# Comparator.net
KiCad netlist of a schematic drawn in Altium Designer
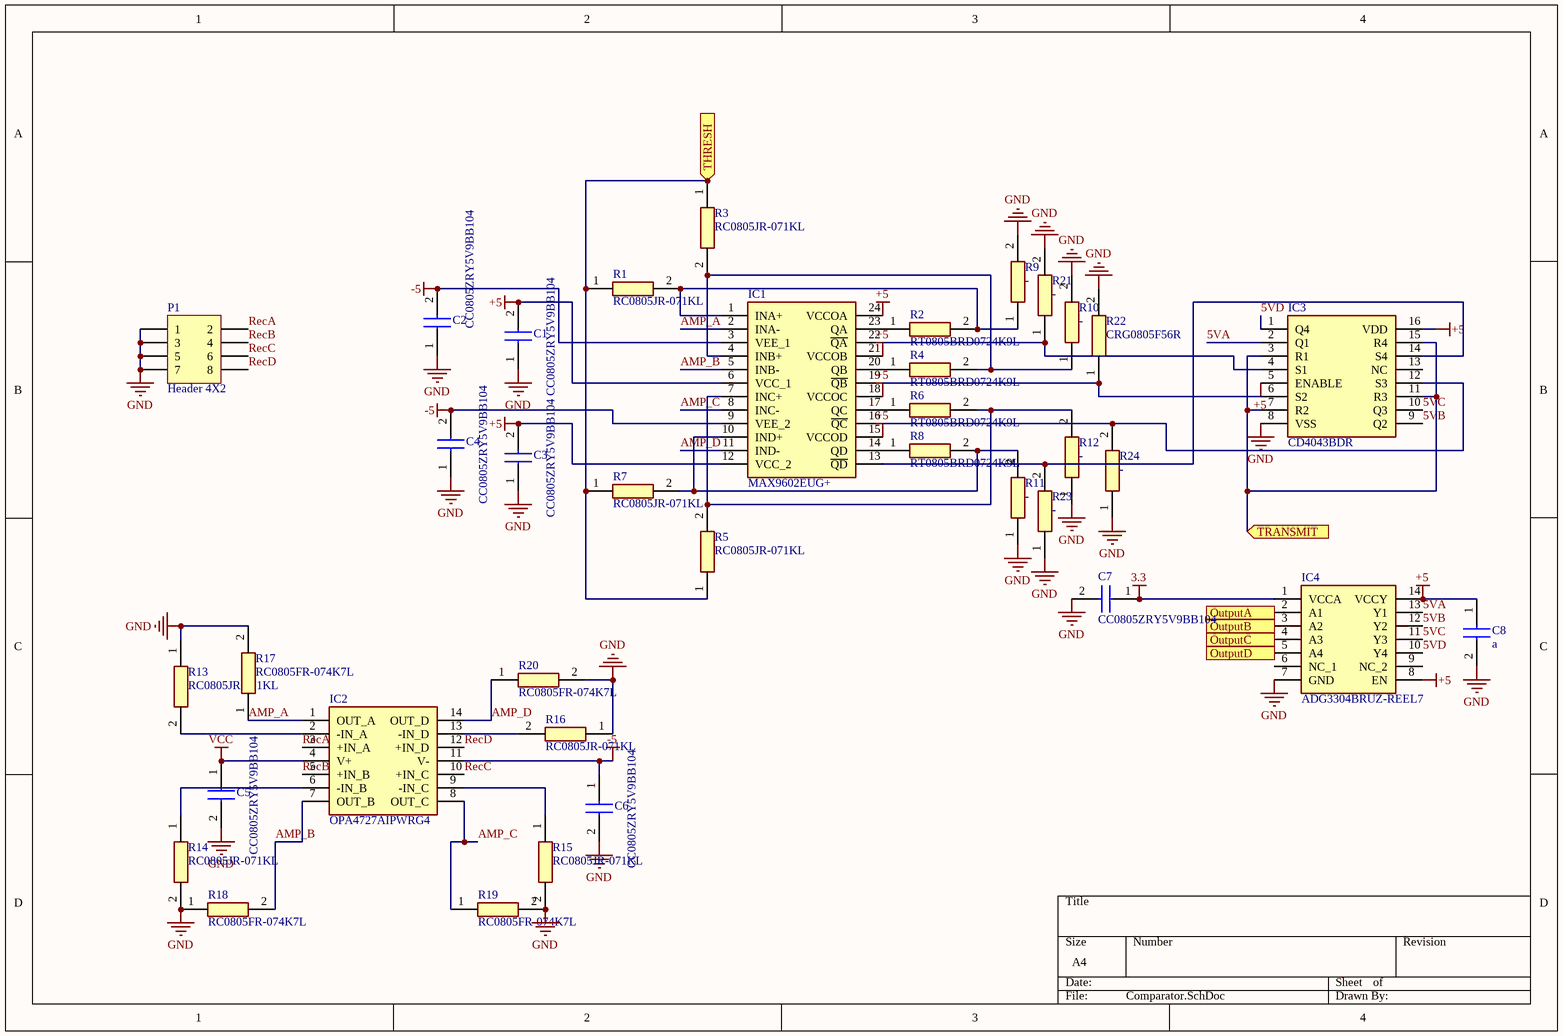
[diagram p0: Comparator.SchDoc]

(export (version "E")
  (design (tool "Eeschema 10.0.6"))
  (components
    (comp (ref "C1")
      (value "CC0805ZRY5V9BB104")
      (footprint "SamacSys:CAPC2013X70N")
      (description "Capacitor")
      (fields (field (name "MOUSER PART NUMBER") "603-CC805ZRY5V9BB104"))
      (libsource (lib "*") (part "CC0805ZRY5V9BB104"))
    )
    (comp (ref "C2")
      (value "CC0805ZRY5V9BB104")
      (footprint "SamacSys:CAPC2013X70N")
      (description "Capacitor")
      (fields (field (name "MOUSER PART NUMBER") "603-CC805ZRY5V9BB104"))
      (libsource (lib "*") (part "CC0805ZRY5V9BB104"))
    )
    (comp (ref "C3")
      (value "CC0805ZRY5V9BB104")
      (footprint "SamacSys:CAPC2013X70N")
      (description "Capacitor")
      (fields (field (name "MOUSER PART NUMBER") "603-CC805ZRY5V9BB104"))
      (libsource (lib "*") (part "CC0805ZRY5V9BB104"))
    )
    (comp (ref "C4")
      (value "CC0805ZRY5V9BB104")
      (footprint "SamacSys:CAPC2013X70N")
      (description "Capacitor")
      (fields (field (name "MOUSER PART NUMBER") "603-CC805ZRY5V9BB104"))
      (libsource (lib "*") (part "CC0805ZRY5V9BB104"))
    )
    (comp (ref "C5")
      (value "CC0805ZRY5V9BB104")
      (footprint "SamacSys:CAPC2013X70N")
      (description "Capacitor")
      (fields (field (name "MOUSER PART NUMBER") "603-CC805ZRY5V9BB104"))
      (libsource (lib "*") (part "CC0805ZRY5V9BB104"))
    )
    (comp (ref "C6")
      (value "CC0805ZRY5V9BB104")
      (footprint "SamacSys:CAPC2013X70N")
      (description "Capacitor")
      (fields (field (name "MOUSER PART NUMBER") "603-CC805ZRY5V9BB104"))
      (libsource (lib "*") (part "CC0805ZRY5V9BB104"))
    )
    (comp (ref "C7")
      (value "CC0805ZRY5V9BB104")
      (footprint "SamacSys:CAPC2013X70N")
      (description "Capacitor")
      (fields (field (name "MOUSER PART NUMBER") "603-CC805ZRY5V9BB104"))
      (libsource (lib "*") (part "CC0805ZRY5V9BB104"))
    )
    (comp (ref "C8")
      (value "a")
      (footprint "SamacSys:CAPC2013X70N")
      (description "Capacitor")
      (fields
        (field (name "MANUFACTURER_PART_NUMBER") "CC0805ZRY5V9BB104")
        (field (name "MOUSER PART NUMBER") "603-CC805ZRY5V9BB104")
      )
      (libsource (lib "*") (part "CC0805ZRY5V9BB104"))
    )
    (comp (ref "IC1")
      (value "MAX9602EUG+")
      (footprint "SamacSys:SOP65P640X110-24N")
      (description "Integrated Circuit")
      (fields (field (name "MOUSER PART NUMBER") "700-MAX9602EUG"))
      (libsource (lib "*") (part "MAX9602EUG+"))
    )
    (comp (ref "IC2")
      (value "OPA4727AIPWRG4")
      (footprint "SamacSys:SOP65P640X120-14N")
      (description "Integrated Circuit")
      (fields (field (name "MOUSER PART NUMBER") "595-OPA4727AIPWRG4"))
      (libsource (lib "*") (part "OPA4727AIPWRG4"))
    )
    (comp (ref "IC3")
      (value "CD4043BDR")
      (footprint "SamacSys:SOIC127P600X175-16N")
      (description "Integrated Circuit")
      (fields (field (name "MOUSER PART NUMBER") "595-CD4043BDR"))
      (libsource (lib "*") (part "CD4043BDR"))
    )
    (comp (ref "IC4")
      (value "ADG3304BRUZ-REEL7")
      (footprint "SamacSys:SOP65P640X120-14N")
      (description "Integrated Circuit")
      (fields (field (name "MOUSER PART NUMBER") "584-ADG3304BRUZ-R7"))
      (libsource (lib "*") (part "ADG3304BRUZ-REEL7"))
    )
    (comp (ref "P1")
      (value "Header 4X2")
      (footprint "HDR2X4")
      (description "Header, 4-Pin, Dual row")
      (fields (field (name "PUBLISHER") "Altium Limited"))
      (libsource (lib "Miscellaneous Connectors") (part "Header 4X2"))
    )
    (comp (ref "R1")
      (value "RC0805JR-071KL")
      (footprint "SamacSys:RESC2012X60N")
      (description "Resistor")
      (fields (field (name "MOUSER PART NUMBER") "603-RC0805JR-071KL"))
      (libsource (lib "") (part "RC0805JR-071KL_1"))
    )
    (comp (ref "R2")
      (value "RT0805BRD0724K9L")
      (footprint "SamacSys:RESC2012X60N")
      (description "Resistor")
      (libsource (lib "*") (part "RT0805BRD0724K9L"))
    )
    (comp (ref "R3")
      (value "RC0805JR-071KL")
      (footprint "SamacSys:RESC2012X60N")
      (description "Resistor")
      (fields (field (name "MOUSER PART NUMBER") "603-RC0805JR-071KL"))
      (libsource (lib "") (part "RC0805JR-071KL_2"))
    )
    (comp (ref "R4")
      (value "RT0805BRD0724K9L")
      (footprint "SamacSys:RESC2012X60N")
      (description "Resistor")
      (libsource (lib "*") (part "RT0805BRD0724K9L"))
    )
    (comp (ref "R5")
      (value "RC0805JR-071KL")
      (footprint "SamacSys:RESC2012X60N")
      (description "Resistor")
      (fields (field (name "MOUSER PART NUMBER") "603-RC0805JR-071KL"))
      (libsource (lib "*") (part "RC0805JR-071KL"))
    )
    (comp (ref "R6")
      (value "RT0805BRD0724K9L")
      (footprint "SamacSys:RESC2012X60N")
      (description "Resistor")
      (libsource (lib "*") (part "RT0805BRD0724K9L"))
    )
    (comp (ref "R7")
      (value "RC0805JR-071KL")
      (footprint "SamacSys:RESC2012X60N")
      (description "Resistor")
      (fields (field (name "MOUSER PART NUMBER") "603-RC0805JR-071KL"))
      (libsource (lib "") (part "RC0805JR-071KL_1"))
    )
    (comp (ref "R8")
      (value "RT0805BRD0724K9L")
      (footprint "SamacSys:RESC2012X60N")
      (description "Resistor")
      (libsource (lib "*") (part "RT0805BRD0724K9L"))
    )
    (comp (ref "R9")
      (value "-")
      (footprint "SamacSys:RESC2012X65N")
      (description "Resistor")
      (fields
        (field (name "MANUFACTURER_PART_NUMBER") "CRG0805F56R")
        (field (name "RS PART NUMBER") "2230269")
      )
      (libsource (lib "*") (part "CRG0805F56R"))
    )
    (comp (ref "R10")
      (value "-")
      (footprint "SamacSys:RESC2012X65N")
      (description "Resistor")
      (fields
        (field (name "MANUFACTURER_PART_NUMBER") "CRG0805F56R")
        (field (name "RS PART NUMBER") "2230269")
      )
      (libsource (lib "*") (part "CRG0805F56R"))
    )
    (comp (ref "R11")
      (value "-")
      (footprint "SamacSys:RESC2012X65N")
      (description "Resistor")
      (fields
        (field (name "MANUFACTURER_PART_NUMBER") "CRG0805F56R")
        (field (name "RS PART NUMBER") "2230269")
      )
      (libsource (lib "*") (part "CRG0805F56R"))
    )
    (comp (ref "R12")
      (value "-")
      (footprint "SamacSys:RESC2012X65N")
      (description "Resistor")
      (fields
        (field (name "MANUFACTURER_PART_NUMBER") "CRG0805F56R")
        (field (name "RS PART NUMBER") "2230269")
      )
      (libsource (lib "*") (part "CRG0805F56R"))
    )
    (comp (ref "R13")
      (value "RC0805JR-071KL")
      (footprint "SamacSys:RESC2012X60N")
      (description "Resistor")
      (fields (field (name "MOUSER PART NUMBER") "603-RC0805JR-071KL"))
      (libsource (lib "") (part "RC0805JR-071KL_2"))
    )
    (comp (ref "R14")
      (value "RC0805JR-071KL")
      (footprint "SamacSys:RESC2012X60N")
      (description "Resistor")
      (fields (field (name "MOUSER PART NUMBER") "603-RC0805JR-071KL"))
      (libsource (lib "") (part "RC0805JR-071KL_2"))
    )
    (comp (ref "R15")
      (value "RC0805JR-071KL")
      (footprint "SamacSys:RESC2012X60N")
      (description "Resistor")
      (fields (field (name "MOUSER PART NUMBER") "603-RC0805JR-071KL"))
      (libsource (lib "") (part "RC0805JR-071KL_2"))
    )
    (comp (ref "R16")
      (value "RC0805JR-071KL")
      (footprint "SamacSys:RESC2012X60N")
      (description "Resistor")
      (fields (field (name "MOUSER PART NUMBER") "603-RC0805JR-071KL"))
      (libsource (lib "") (part "RC0805JR-071KL_3"))
    )
    (comp (ref "R17")
      (value "RC0805FR-074K7L")
      (footprint "SamacSys:RESC2012X60N")
      (description "Resistor")
      (fields
        (field (name "MOUSER PART NUMBER") "603-RC0805FR-074K7L")
        (field (name "RS PART NUMBER") "6181408")
      )
      (libsource (lib "") (part "RC0805FR-074K7L_1"))
    )
    (comp (ref "R18")
      (value "RC0805FR-074K7L")
      (footprint "SamacSys:RESC2012X60N")
      (description "Resistor")
      (fields
        (field (name "MOUSER PART NUMBER") "603-RC0805FR-074K7L")
        (field (name "RS PART NUMBER") "6181408")
      )
      (libsource (lib "*") (part "RC0805FR-074K7L"))
    )
    (comp (ref "R19")
      (value "RC0805FR-074K7L")
      (footprint "SamacSys:RESC2012X60N")
      (description "Resistor")
      (fields
        (field (name "MOUSER PART NUMBER") "603-RC0805FR-074K7L")
        (field (name "RS PART NUMBER") "6181408")
      )
      (libsource (lib "*") (part "RC0805FR-074K7L"))
    )
    (comp (ref "R20")
      (value "RC0805FR-074K7L")
      (footprint "SamacSys:RESC2012X60N")
      (description "Resistor")
      (fields
        (field (name "MOUSER PART NUMBER") "603-RC0805FR-074K7L")
        (field (name "RS PART NUMBER") "6181408")
      )
      (libsource (lib "*") (part "RC0805FR-074K7L"))
    )
    (comp (ref "R21")
      (value "-")
      (footprint "SamacSys:RESC2012X65N")
      (description "Resistor")
      (fields
        (field (name "MANUFACTURER_PART_NUMBER") "CRG0805F56R")
        (field (name "RS PART NUMBER") "2230269")
      )
      (libsource (lib "*") (part "CRG0805F56R"))
    )
    (comp (ref "R22")
      (value "CRG0805F56R")
      (footprint "SamacSys:RESC2012X65N")
      (description "Resistor")
      (fields (field (name "RS PART NUMBER") "2230269"))
      (libsource (lib "*") (part "CRG0805F56R"))
    )
    (comp (ref "R23")
      (value "-")
      (footprint "SamacSys:RESC2012X65N")
      (description "Resistor")
      (fields
        (field (name "MANUFACTURER_PART_NUMBER") "CRG0805F56R")
        (field (name "RS PART NUMBER") "2230269")
      )
      (libsource (lib "*") (part "CRG0805F56R"))
    )
    (comp (ref "R24")
      (value "-")
      (footprint "SamacSys:RESC2012X65N")
      (description "Resistor")
      (fields
        (field (name "MANUFACTURER_PART_NUMBER") "CRG0805F56R")
        (field (name "RS PART NUMBER") "2230269")
      )
      (libsource (lib "*") (part "CRG0805F56R"))
    )
  )
  (nets
    (net (code "1") (name "+5") (class "Default")
      (node (ref "C1") (pin "2") (pinfunction "C2_2") (pintype "passive"))
      (node (ref "C3") (pin "2") (pinfunction "C2_2") (pintype "passive"))
      (node (ref "C8") (pin "1") (pinfunction "C1_1") (pintype "passive"))
      (node (ref "IC1") (pin "12") (pinfunction "VCC_2_12") (pintype "passive"))
      (node (ref "IC1") (pin "15") (pinfunction "VCCOD_15") (pintype "passive"))
      (node (ref "IC1") (pin "18") (pinfunction "VCCOC_18") (pintype "passive"))
      (node (ref "IC1") (pin "21") (pinfunction "VCCOB_21") (pintype "passive"))
      (node (ref "IC1") (pin "24") (pinfunction "VCCOA_24") (pintype "passive"))
      (node (ref "IC1") (pin "6") (pinfunction "VCC_1_6") (pintype "passive"))
      (node (ref "IC3") (pin "16") (pinfunction "VDD_16") (pintype "passive"))
      (node (ref "IC3") (pin "5") (pinfunction "ENABLE_5") (pintype "passive"))
      (node (ref "IC4") (pin "14") (pinfunction "VCCY_14") (pintype "passive"))
      (node (ref "IC4") (pin "8") (pinfunction "EN_8") (pintype "passive"))
    )
    (net (code "2") (name "-5") (class "Default")
      (node (ref "C2") (pin "2") (pinfunction "C2_2") (pintype "passive"))
      (node (ref "C4") (pin "2") (pinfunction "C2_2") (pintype "passive"))
      (node (ref "C6") (pin "1") (pinfunction "C1_1") (pintype "passive"))
      (node (ref "IC1") (pin "3") (pinfunction "VEE_1_3") (pintype "passive"))
      (node (ref "IC1") (pin "9") (pinfunction "VEE_2_9") (pintype "passive"))
      (node (ref "IC2") (pin "11") (pinfunction "V-_11") (pintype "passive"))
    )
    (net (code "3") (name "/5VA") (class "Default")
      (node (ref "IC3") (pin "2") (pinfunction "Q1_2") (pintype "passive"))
      (node (ref "IC4") (pin "13") (pinfunction "Y1_13") (pintype "passive"))
    )
    (net (code "4") (name "/5VB") (class "Default")
      (node (ref "IC3") (pin "9") (pinfunction "Q2_9") (pintype "passive"))
      (node (ref "IC4") (pin "12") (pinfunction "Y2_12") (pintype "passive"))
    )
    (net (code "5") (name "/5VC") (class "Default")
      (node (ref "IC3") (pin "10") (pinfunction "Q3_10") (pintype "passive"))
      (node (ref "IC4") (pin "11") (pinfunction "Y3_11") (pintype "passive"))
    )
    (net (code "6") (name "/5VD") (class "Default")
      (node (ref "IC3") (pin "1") (pinfunction "Q4_1") (pintype "passive"))
      (node (ref "IC4") (pin "10") (pinfunction "Y4_10") (pintype "passive"))
    )
    (net (code "7") (name "/AMP_A") (class "Default")
      (node (ref "IC1") (pin "2") (pinfunction "INA-_2") (pintype "passive"))
      (node (ref "IC2") (pin "1") (pinfunction "OUT_A_1") (pintype "passive"))
      (node (ref "R17") (pin "1") (pinfunction "1_1") (pintype "passive"))
    )
    (net (code "8") (name "/AMP_B") (class "Default")
      (node (ref "IC1") (pin "5") (pinfunction "INB-_5") (pintype "passive"))
      (node (ref "IC2") (pin "7") (pinfunction "OUT_B_7") (pintype "passive"))
      (node (ref "R18") (pin "2") (pinfunction "2_2") (pintype "passive"))
    )
    (net (code "9") (name "/AMP_C") (class "Default")
      (node (ref "IC1") (pin "8") (pinfunction "INC-_8") (pintype "passive"))
      (node (ref "IC2") (pin "8") (pinfunction "OUT_C_8") (pintype "passive"))
      (node (ref "R19") (pin "1") (pinfunction "1_1") (pintype "passive"))
    )
    (net (code "10") (name "/AMP_D") (class "Default")
      (node (ref "IC1") (pin "11") (pinfunction "IND-_11") (pintype "passive"))
      (node (ref "IC2") (pin "14") (pinfunction "OUT_D_14") (pintype "passive"))
      (node (ref "R20") (pin "1") (pinfunction "1_1") (pintype "passive"))
    )
    (net (code "11") (name "/OutputA") (class "Default")
      (node (ref "IC4") (pin "2") (pinfunction "A1_2") (pintype "passive"))
    )
    (net (code "12") (name "/OutputB") (class "Default")
      (node (ref "IC4") (pin "3") (pinfunction "A2_3") (pintype "passive"))
    )
    (net (code "13") (name "/OutputC") (class "Default")
      (node (ref "IC4") (pin "4") (pinfunction "A3_4") (pintype "passive"))
    )
    (net (code "14") (name "/OutputD") (class "Default")
      (node (ref "IC4") (pin "5") (pinfunction "A4_5") (pintype "passive"))
    )
    (net (code "15") (name "/RecA") (class "Default")
      (node (ref "IC2") (pin "3") (pinfunction "+IN_A_3") (pintype "passive"))
      (node (ref "P1") (pin "2") (pinfunction "2_2") (pintype "passive"))
    )
    (net (code "16") (name "/RecB") (class "Default")
      (node (ref "IC2") (pin "5") (pinfunction "+IN_B_5") (pintype "passive"))
      (node (ref "P1") (pin "4") (pinfunction "4_4") (pintype "passive"))
    )
    (net (code "17") (name "/RecC") (class "Default")
      (node (ref "IC2") (pin "10") (pinfunction "+IN_C_10") (pintype "passive"))
      (node (ref "P1") (pin "6") (pinfunction "6_6") (pintype "passive"))
    )
    (net (code "18") (name "/RecD") (class "Default")
      (node (ref "IC2") (pin "12") (pinfunction "+IN_D_12") (pintype "passive"))
      (node (ref "P1") (pin "8") (pinfunction "8_8") (pintype "passive"))
    )
    (net (code "19") (name "/THRESH") (class "Default")
      (node (ref "R1") (pin "1") (pinfunction "1_1") (pintype "passive"))
      (node (ref "R3") (pin "1") (pinfunction "1_1") (pintype "passive"))
      (node (ref "R5") (pin "1") (pinfunction "1_1") (pintype "passive"))
      (node (ref "R7") (pin "1") (pinfunction "1_1") (pintype "passive"))
    )
    (net (code "20") (name "/TRANSMIT") (class "Default")
      (node (ref "IC3") (pin "11") (pinfunction "R3_11") (pintype "passive"))
      (node (ref "IC3") (pin "15") (pinfunction "R4_15") (pintype "passive"))
      (node (ref "IC3") (pin "3") (pinfunction "R1_3") (pintype "passive"))
      (node (ref "IC3") (pin "7") (pinfunction "R2_7") (pintype "passive"))
    )
    (net (code "21") (name "3.3") (class "Default")
      (node (ref "C7") (pin "1") (pinfunction "C1_1") (pintype "passive"))
      (node (ref "IC4") (pin "1") (pinfunction "VCCA_1") (pintype "passive"))
    )
    (net (code "22") (name "GND") (class "Default")
      (node (ref "C1") (pin "1") (pinfunction "C1_1") (pintype "passive"))
      (node (ref "C2") (pin "1") (pinfunction "C1_1") (pintype "passive"))
      (node (ref "C3") (pin "1") (pinfunction "C1_1") (pintype "passive"))
      (node (ref "C4") (pin "1") (pinfunction "C1_1") (pintype "passive"))
      (node (ref "C5") (pin "2") (pinfunction "C2_2") (pintype "passive"))
      (node (ref "C6") (pin "2") (pinfunction "C2_2") (pintype "passive"))
      (node (ref "C7") (pin "2") (pinfunction "C2_2") (pintype "passive"))
      (node (ref "C8") (pin "2") (pinfunction "C2_2") (pintype "passive"))
      (node (ref "IC3") (pin "8") (pinfunction "VSS_8") (pintype "passive"))
      (node (ref "IC4") (pin "7") (pinfunction "GND_7") (pintype "passive"))
      (node (ref "P1") (pin "1") (pinfunction "1_1") (pintype "passive"))
      (node (ref "P1") (pin "3") (pinfunction "3_3") (pintype "passive"))
      (node (ref "P1") (pin "5") (pinfunction "5_5") (pintype "passive"))
      (node (ref "P1") (pin "7") (pinfunction "7_7") (pintype "passive"))
      (node (ref "R10") (pin "2") (pinfunction "2_2") (pintype "passive"))
      (node (ref "R11") (pin "1") (pinfunction "1_1") (pintype "passive"))
      (node (ref "R12") (pin "1") (pinfunction "1_1") (pintype "passive"))
      (node (ref "R13") (pin "1") (pinfunction "1_1") (pintype "passive"))
      (node (ref "R14") (pin "2") (pinfunction "2_2") (pintype "passive"))
      (node (ref "R15") (pin "2") (pinfunction "2_2") (pintype "passive"))
      (node (ref "R16") (pin "1") (pinfunction "1_1") (pintype "passive"))
      (node (ref "R17") (pin "2") (pinfunction "2_2") (pintype "passive"))
      (node (ref "R18") (pin "1") (pinfunction "1_1") (pintype "passive"))
      (node (ref "R19") (pin "2") (pinfunction "2_2") (pintype "passive"))
      (node (ref "R20") (pin "2") (pinfunction "2_2") (pintype "passive"))
      (node (ref "R21") (pin "2") (pinfunction "2_2") (pintype "passive"))
      (node (ref "R22") (pin "2") (pinfunction "2_2") (pintype "passive"))
      (node (ref "R23") (pin "1") (pinfunction "1_1") (pintype "passive"))
      (node (ref "R24") (pin "1") (pinfunction "1_1") (pintype "passive"))
      (node (ref "R9") (pin "2") (pinfunction "2_2") (pintype "passive"))
    )
    (net (code "23") (name "Net-(IC1-INA+)") (class "Default")
      (node (ref "IC1") (pin "1") (pinfunction "INA+_1") (pintype "passive"))
      (node (ref "R1") (pin "2") (pinfunction "2_2") (pintype "passive"))
      (node (ref "R2") (pin "2") (pinfunction "2_2") (pintype "passive"))
      (node (ref "R9") (pin "1") (pinfunction "1_1") (pintype "passive"))
    )
    (net (code "24") (name "Net-(IC1-INB+)") (class "Default")
      (node (ref "IC1") (pin "4") (pinfunction "INB+_4") (pintype "passive"))
      (node (ref "R10") (pin "1") (pinfunction "1_1") (pintype "passive"))
      (node (ref "R3") (pin "2") (pinfunction "2_2") (pintype "passive"))
      (node (ref "R4") (pin "2") (pinfunction "2_2") (pintype "passive"))
    )
    (net (code "25") (name "Net-(IC1-INC+)") (class "Default")
      (node (ref "IC1") (pin "7") (pinfunction "INC+_7") (pintype "passive"))
      (node (ref "R12") (pin "2") (pinfunction "2_2") (pintype "passive"))
      (node (ref "R5") (pin "2") (pinfunction "2_2") (pintype "passive"))
      (node (ref "R6") (pin "2") (pinfunction "2_2") (pintype "passive"))
    )
    (net (code "26") (name "Net-(IC1-IND+)") (class "Default")
      (node (ref "IC1") (pin "10") (pinfunction "IND+_10") (pintype "passive"))
      (node (ref "R11") (pin "2") (pinfunction "2_2") (pintype "passive"))
      (node (ref "R7") (pin "2") (pinfunction "2_2") (pintype "passive"))
      (node (ref "R8") (pin "2") (pinfunction "2_2") (pintype "passive"))
    )
    (net (code "27") (name "Net-(IC1-QA)") (class "Default")
      (node (ref "IC1") (pin "23") (pinfunction "QA_23") (pintype "passive"))
      (node (ref "R2") (pin "1") (pinfunction "1_1") (pintype "passive"))
    )
    (net (code "28") (name "Net-(IC1-QB)") (class "Default")
      (node (ref "IC1") (pin "20") (pinfunction "QB_20") (pintype "passive"))
      (node (ref "R4") (pin "1") (pinfunction "1_1") (pintype "passive"))
    )
    (net (code "29") (name "Net-(IC1-QC)") (class "Default")
      (node (ref "IC1") (pin "17") (pinfunction "QC_17") (pintype "passive"))
      (node (ref "R6") (pin "1") (pinfunction "1_1") (pintype "passive"))
    )
    (net (code "30") (name "Net-(IC1-QD)") (class "Default")
      (node (ref "IC1") (pin "14") (pinfunction "QD_14") (pintype "passive"))
      (node (ref "R8") (pin "1") (pinfunction "1_1") (pintype "passive"))
    )
    (net (code "31") (name "Net-(IC1-~{QA})") (class "Default")
      (node (ref "IC1") (pin "22") (pinfunction "~{QA}_22") (pintype "passive"))
      (node (ref "IC3") (pin "4") (pinfunction "S1_4") (pintype "passive"))
      (node (ref "R21") (pin "1") (pinfunction "1_1") (pintype "passive"))
    )
    (net (code "32") (name "Net-(IC1-~{QB})") (class "Default")
      (node (ref "IC1") (pin "19") (pinfunction "~{QB}_19") (pintype "passive"))
      (node (ref "IC3") (pin "6") (pinfunction "S2_6") (pintype "passive"))
      (node (ref "R22") (pin "1") (pinfunction "1_1") (pintype "passive"))
    )
    (net (code "33") (name "Net-(IC1-~{QC})") (class "Default")
      (node (ref "IC1") (pin "16") (pinfunction "~{QC}_16") (pintype "passive"))
      (node (ref "IC3") (pin "12") (pinfunction "S3_12") (pintype "passive"))
      (node (ref "R24") (pin "2") (pinfunction "2_2") (pintype "passive"))
    )
    (net (code "34") (name "Net-(IC1-~{QD})") (class "Default")
      (node (ref "IC1") (pin "13") (pinfunction "~{QD}_13") (pintype "passive"))
      (node (ref "IC3") (pin "14") (pinfunction "S4_14") (pintype "passive"))
      (node (ref "R23") (pin "2") (pinfunction "2_2") (pintype "passive"))
    )
    (net (code "35") (name "Net-(IC2--IN_A)") (class "Default")
      (node (ref "IC2") (pin "2") (pinfunction "-IN_A_2") (pintype "passive"))
      (node (ref "R13") (pin "2") (pinfunction "2_2") (pintype "passive"))
    )
    (net (code "36") (name "Net-(IC2--IN_B)") (class "Default")
      (node (ref "IC2") (pin "6") (pinfunction "-IN_B_6") (pintype "passive"))
      (node (ref "R14") (pin "1") (pinfunction "1_1") (pintype "passive"))
    )
    (net (code "37") (name "Net-(IC2--IN_C)") (class "Default")
      (node (ref "IC2") (pin "9") (pinfunction "-IN_C_9") (pintype "passive"))
      (node (ref "R15") (pin "1") (pinfunction "1_1") (pintype "passive"))
    )
    (net (code "38") (name "Net-(IC2--IN_D)") (class "Default")
      (node (ref "IC2") (pin "13") (pinfunction "-IN_D_13") (pintype "passive"))
      (node (ref "R16") (pin "2") (pinfunction "2_2") (pintype "passive"))
    )
    (net (code "39") (name "VCC") (class "Default")
      (node (ref "C5") (pin "1") (pinfunction "C1_1") (pintype "passive"))
      (node (ref "IC2") (pin "4") (pinfunction "V+_4") (pintype "passive"))
    )
    (net (code "40") (name "unconnected-(IC3-NC-Pad13)") (class "Default")
      (node (ref "IC3") (pin "13") (pinfunction "NC_13") (pintype "passive"))
    )
    (net (code "41") (name "unconnected-(IC4-NC_1-Pad6)") (class "Default")
      (node (ref "IC4") (pin "6") (pinfunction "NC_1_6") (pintype "passive"))
    )
    (net (code "42") (name "unconnected-(IC4-NC_2-Pad9)") (class "Default")
      (node (ref "IC4") (pin "9") (pinfunction "NC_2_9") (pintype "passive"))
    )
  )
)
